# Driver_motor_L298N.net
KiCad netlist of a schematic drawn in EAGLE
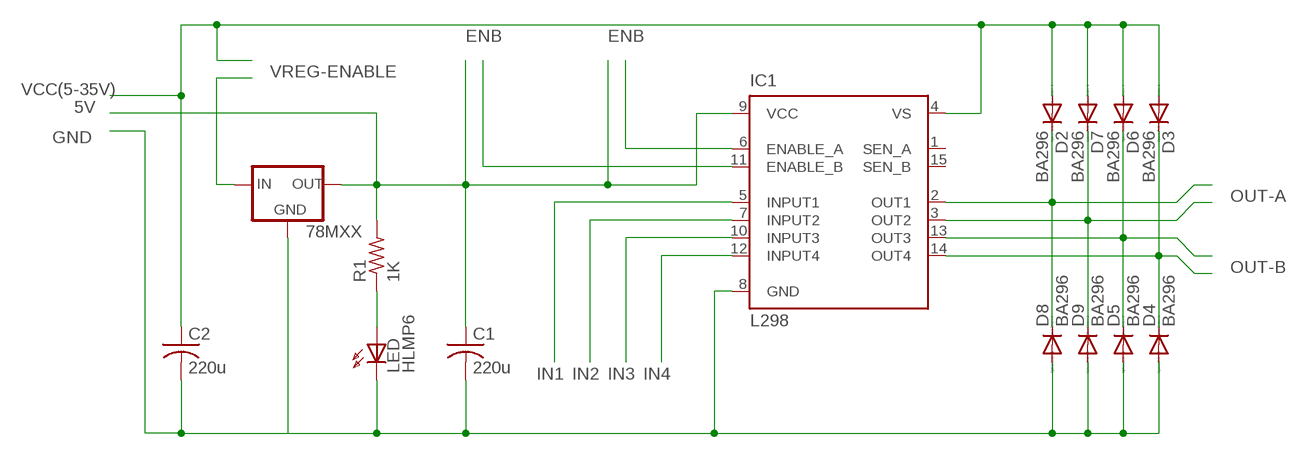
[diagram p0: schematic, sheet 1]

(export (version "E")
  (design (tool "Eeschema 10.0.6"))
  (components
    (comp (ref "78MXX")
      (value "78LXX")
      (footprint "eagle-import:78LXX")
      (libsource (lib "eagle-import") (part "78LXX"))
    )
    (comp (ref "C1")
      (value "220u")
      (footprint "eagle-import:C025-024X044")
      (libsource (lib "eagle-import") (part "C-US025-024X044"))
    )
    (comp (ref "C2")
      (value "220u")
      (footprint "eagle-import:C025-024X044")
      (libsource (lib "eagle-import") (part "C-US025-024X044"))
    )
    (comp (ref "D2")
      (value "BA296")
      (footprint "eagle-import:P2-15")
      (libsource (lib "eagle-import") (part "BA296"))
    )
    (comp (ref "D3")
      (value "BA296")
      (footprint "eagle-import:P2-15")
      (libsource (lib "eagle-import") (part "BA296"))
    )
    (comp (ref "D4")
      (value "BA296")
      (footprint "eagle-import:P2-15")
      (libsource (lib "eagle-import") (part "BA296"))
    )
    (comp (ref "D5")
      (value "BA296")
      (footprint "eagle-import:P2-15")
      (libsource (lib "eagle-import") (part "BA296"))
    )
    (comp (ref "D6")
      (value "BA296")
      (footprint "eagle-import:P2-15")
      (libsource (lib "eagle-import") (part "BA296"))
    )
    (comp (ref "D7")
      (value "BA296")
      (footprint "eagle-import:P2-15")
      (libsource (lib "eagle-import") (part "BA296"))
    )
    (comp (ref "D8")
      (value "BA296")
      (footprint "eagle-import:P2-15")
      (libsource (lib "eagle-import") (part "BA296"))
    )
    (comp (ref "D9")
      (value "BA296")
      (footprint "eagle-import:P2-15")
      (libsource (lib "eagle-import") (part "BA296"))
    )
    (comp (ref "IC1")
      (value "L298")
      (footprint "eagle-import:MULTIWATT-15")
      (fields (field (name "MPN") "L298N"))
      (libsource (lib "eagle-import") (part "L298"))
    )
    (comp (ref "LED")
      (value "HLMP6")
      (footprint "eagle-import:HLMP6")
      (fields (field (name "MF") "AGILENT TECHNOLOGIES") (field (name "MPN") "HLMP-6500"))
      (libsource (lib "eagle-import") (part "HLMP6"))
    )
    (comp (ref "R1")
      (value "1K")
      (footprint "eagle-import:0204V")
      (libsource (lib "eagle-import") (part "R-US_0204/2V"))
    )
  )
  (nets
    (net (code "1") (name "/5V") (class "Default")
      (node (ref "78MXX") (pin "OUT") (pinfunction "OUT_OUT") (pintype "passive"))
      (node (ref "C1") (pin "1") (pinfunction "1_1") (pintype "passive"))
      (node (ref "IC1") (pin "9") (pinfunction "VCC_9") (pintype "power_in"))
      (node (ref "R1") (pin "2") (pinfunction "2_2") (pintype "passive"))
    )
    (net (code "2") (name "/GND") (class "Default")
      (node (ref "C1") (pin "2") (pinfunction "2_2") (pintype "passive"))
      (node (ref "C2") (pin "2") (pinfunction "2_2") (pintype "passive"))
      (node (ref "D4") (pin "A") (pinfunction "A_A") (pintype "passive"))
      (node (ref "D5") (pin "A") (pinfunction "A_A") (pintype "passive"))
      (node (ref "D8") (pin "A") (pinfunction "A_A") (pintype "passive"))
      (node (ref "D9") (pin "A") (pinfunction "A_A") (pintype "passive"))
      (node (ref "IC1") (pin "8") (pinfunction "GND_8") (pintype "power_in"))
      (node (ref "LED") (pin "K") (pinfunction "K_K") (pintype "passive"))
    )
    (net (code "3") (name "/IN1") (class "Default")
      (node (ref "IC1") (pin "5") (pinfunction "INPUT1_5") (pintype "input"))
    )
    (net (code "4") (name "/IN2") (class "Default")
      (node (ref "IC1") (pin "7") (pinfunction "INPUT2_7") (pintype "input"))
    )
    (net (code "5") (name "/IN3") (class "Default")
      (node (ref "IC1") (pin "10") (pinfunction "INPUT3_10") (pintype "input"))
    )
    (net (code "6") (name "/IN4") (class "Default")
      (node (ref "IC1") (pin "12") (pinfunction "INPUT4_12") (pintype "input"))
    )
    (net (code "7") (name "/OUT-A") (class "Default")
      (node (ref "D2") (pin "C") (pinfunction "C_C") (pintype "passive"))
      (node (ref "D8") (pin "C") (pinfunction "C_C") (pintype "passive"))
      (node (ref "IC1") (pin "2") (pinfunction "OUT1_2") (pintype "output"))
    )
    (net (code "8") (name "/OUT-B") (class "Default")
      (node (ref "D5") (pin "C") (pinfunction "C_C") (pintype "passive"))
      (node (ref "D6") (pin "C") (pinfunction "C_C") (pintype "passive"))
      (node (ref "IC1") (pin "13") (pinfunction "OUT3_13") (pintype "output"))
    )
    (net (code "9") (name "/VCC(5-35V)") (class "Default")
      (node (ref "C2") (pin "1") (pinfunction "1_1") (pintype "passive"))
      (node (ref "D2") (pin "A") (pinfunction "A_A") (pintype "passive"))
      (node (ref "D3") (pin "A") (pinfunction "A_A") (pintype "passive"))
      (node (ref "D6") (pin "A") (pinfunction "A_A") (pintype "passive"))
      (node (ref "D7") (pin "A") (pinfunction "A_A") (pintype "passive"))
      (node (ref "IC1") (pin "4") (pinfunction "VS_4") (pintype "power_in"))
    )
    (net (code "10") (name "/VREG-ENABLE") (class "Default")
      (node (ref "78MXX") (pin "IN") (pinfunction "IN_IN") (pintype "input"))
    )
    (net (code "11") (name "Net-(IC1-OUT2)") (class "Default")
      (node (ref "D7") (pin "C") (pinfunction "C_C") (pintype "passive"))
      (node (ref "D9") (pin "C") (pinfunction "C_C") (pintype "passive"))
      (node (ref "IC1") (pin "3") (pinfunction "OUT2_3") (pintype "output"))
    )
    (net (code "12") (name "Net-(IC1-OUT4)") (class "Default")
      (node (ref "D3") (pin "C") (pinfunction "C_C") (pintype "passive"))
      (node (ref "D4") (pin "C") (pinfunction "C_C") (pintype "passive"))
      (node (ref "IC1") (pin "14") (pinfunction "OUT4_14") (pintype "output"))
    )
    (net (code "13") (name "Net-(LED-PadA)") (class "Default")
      (node (ref "LED") (pin "A") (pinfunction "A_A") (pintype "passive"))
      (node (ref "R1") (pin "1") (pinfunction "1_1") (pintype "passive"))
    )
    (net (code "14") (name "unconnected-(78MXX-PadGND)") (class "Default")
      (node (ref "78MXX") (pin "GND") (pinfunction "GND_GND") (pintype "input"))
    )
    (net (code "15") (name "unconnected-(IC1-ENABLE_A-Pad6)") (class "Default")
      (node (ref "IC1") (pin "6") (pinfunction "ENABLE_A_6") (pintype "input"))
    )
    (net (code "16") (name "unconnected-(IC1-ENABLE_B-Pad11)") (class "Default")
      (node (ref "IC1") (pin "11") (pinfunction "ENABLE_B_11") (pintype "input"))
    )
    (net (code "17") (name "unconnected-(IC1-SEN_A-Pad1)") (class "Default")
      (node (ref "IC1") (pin "1") (pinfunction "SEN_A_1") (pintype "input"))
    )
    (net (code "18") (name "unconnected-(IC1-SEN_B-Pad15)") (class "Default")
      (node (ref "IC1") (pin "15") (pinfunction "SEN_B_15") (pintype "input"))
    )
  )
)
